# DS627-1_1-A.net
KiCad netlist of a schematic drawn in Altium Designer
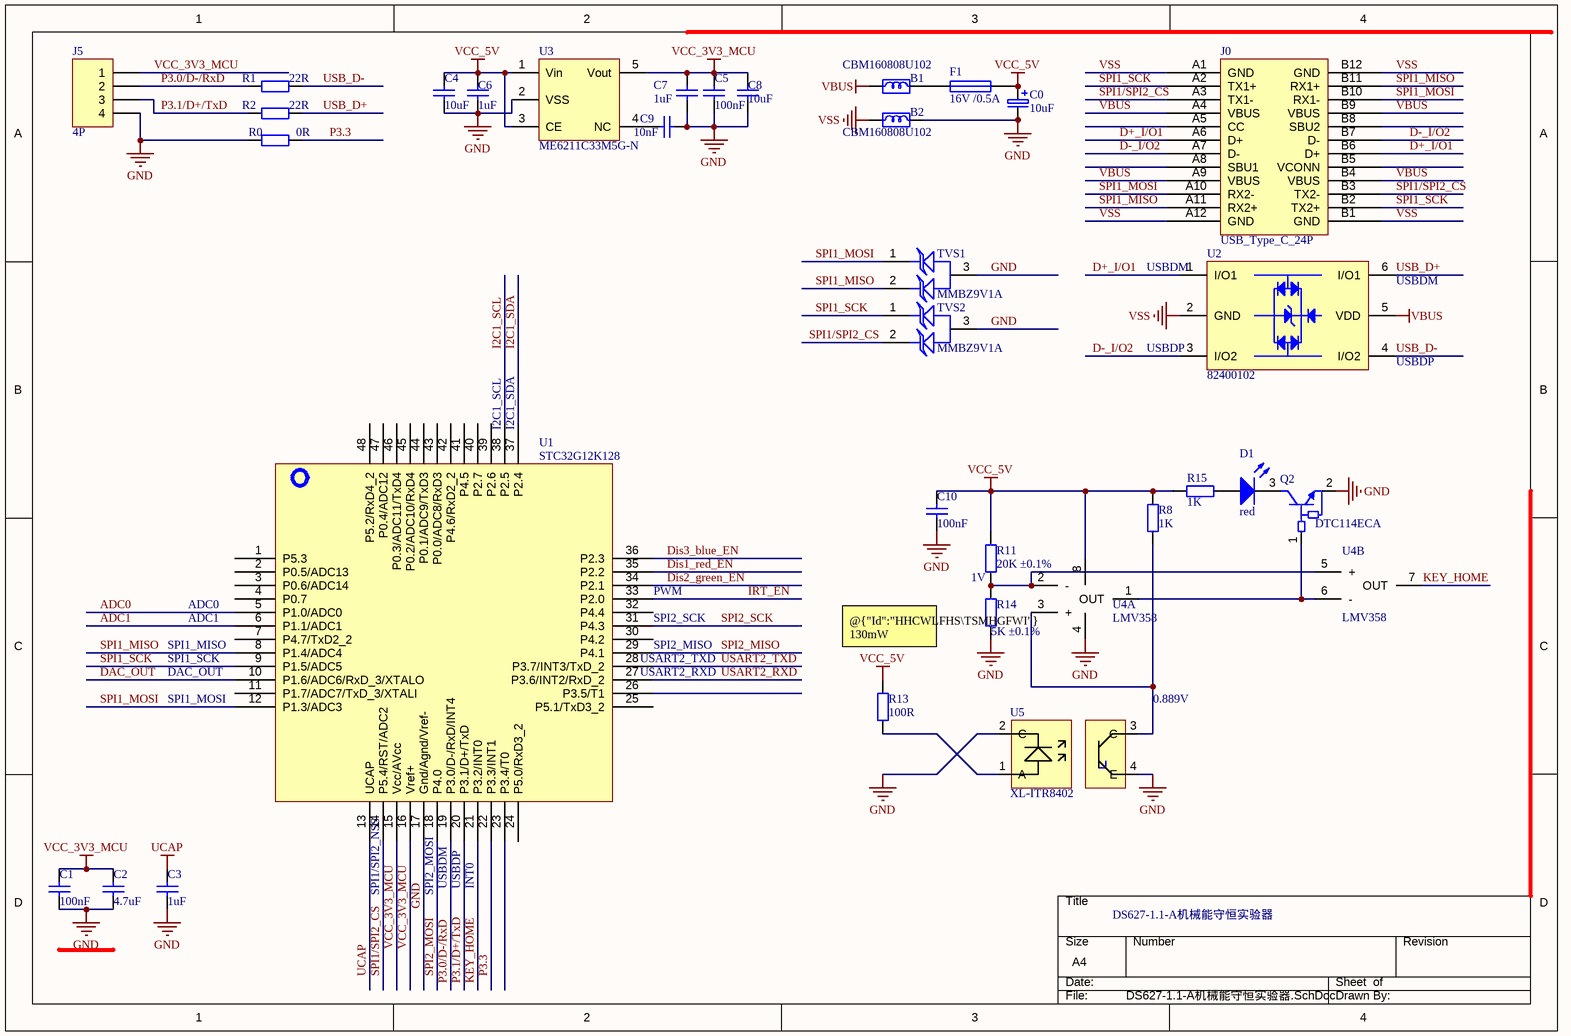
[diagram p0: DS627-1.1-A机械能守恒实验器.SchDoc]

(export (version "E")
  (design (tool "Eeschema 10.0.6"))
  (components
    (comp (ref "B1")
      (value "CBM160808U102")
      (footprint "0603Bead")
      (description "贴片磁珠")
      (libsource (lib "AD_SCH") (part "Chip Ferrite Bead 0606"))
    )
    (comp (ref "B2")
      (value "CBM160808U102")
      (footprint "0603Bead")
      (description "贴片磁珠")
      (libsource (lib "AD_SCH") (part "Chip Ferrite Bead 0606"))
    )
    (comp (ref "C0")
      (value "10uF")
      (footprint "AVX_3216-18(1206)_SMD")
      (description "钽电容")
      (fields (field (name "Comment") "AVX_10uF/16V ±10％(C106)"))
      (libsource (lib "AD_SCH") (part "AVX_10uF/16V ±10％(C106)"))
    )
    (comp (ref "C1")
      (value "100nF")
      (footprint "0603CAP")
      (description "贴片电容")
      (fields (field (name "Comment") "SMDCAP00013"))
      (libsource (lib "AD_SCH") (part "MLCC 100nF 50V ±10％ 0603"))
    )
    (comp (ref "C2")
      (value "4.7uF")
      (footprint "0603CAP")
      (description "贴片电容")
      (fields (field (name "Comment") "SMDCAP00012"))
      (libsource (lib "AD_SCH") (part "MLCC 4.7uF 50V ±10％ 0603"))
    )
    (comp (ref "C3")
      (value "1uF")
      (footprint "0603CAP")
      (description "贴片电容")
      (fields (field (name "Comment") "SMDCAP00015"))
      (libsource (lib "AD_SCH") (part "MLCC 1uF 50V ±10％ 0603"))
    )
    (comp (ref "C4")
      (value "10uF")
      (footprint "1206CAP")
      (description "贴片电容")
      (fields (field (name "Comment") "MLCC 10uF 50V ±20％ 1206"))
      (libsource (lib "AD_SCH") (part "MLCC 10uF 50V ±20％ 1206"))
    )
    (comp (ref "C5")
      (value "100nF")
      (footprint "0603CAP")
      (description "贴片电容")
      (fields (field (name "Comment") "SMDCAP00013"))
      (libsource (lib "AD_SCH") (part "MLCC 100nF 50V ±10％ 0603"))
    )
    (comp (ref "C6")
      (value "1uF")
      (footprint "0603CAP")
      (description "贴片电容")
      (fields (field (name "Comment") "SMDCAP00015"))
      (libsource (lib "AD_SCH") (part "MLCC 1uF 50V ±10％ 0603"))
    )
    (comp (ref "C7")
      (value "1uF")
      (footprint "0603CAP")
      (description "贴片电容")
      (fields (field (name "Comment") "SMDCAP00015"))
      (libsource (lib "AD_SCH") (part "MLCC 1uF 50V ±10％ 0603"))
    )
    (comp (ref "C8")
      (value "10uF")
      (footprint "1206CAP")
      (description "贴片电容")
      (fields (field (name "Comment") "MLCC 10uF 50V ±20％ 1206"))
      (libsource (lib "AD_SCH") (part "MLCC 10uF 50V ±20％ 1206"))
    )
    (comp (ref "C9")
      (value "10nF")
      (footprint "0603CAP")
      (description "贴片电容")
      (fields (field (name "Comment") "SMDCAP00010"))
      (libsource (lib "AD_SCH") (part "MLCC 10nF 50V ±10％ 0603"))
    )
    (comp (ref "C10")
      (value "100nF")
      (footprint "0603CAP")
      (description "贴片电容")
      (fields (field (name "Comment") "SMDCAP00013"))
      (libsource (lib "AD_SCH") (part "MLCC 100nF 50V ±10％ 0603"))
    )
    (comp (ref "D1")
      (value "red")
      (footprint "LED_3mm_red")
      (description "插件LED")
      (fields (field (name "Comment") "Φ3 透明发红 DIP2"))
      (libsource (lib "AD_SCH") (part "Φ3 透明发红 DIP2"))
    )
    (comp (ref "F1")
      (value "16V /0.5A")
      (footprint "1206FUSE")
      (description "贴片自恢复保险丝 16V /0.5A")
      (fields (field (name "Comment") "SMD1206-050C-16V"))
      (libsource (lib "AD_SCH") (part "SMD1206-050C-16V"))
    )
    (comp (ref "J0")
      (value "USB_Type_C_24P")
      (footprint "USB_TYPE_C_24P_Receptacle")
      (libsource (lib "AD_SCH") (part "USB_Type_C_24P"))
    )
    (comp (ref "J5")
      (value "4P")
      (footprint "H4")
      (description "单排直针")
      (fields (field (name "Comment") "DIP4单排直针  间距2mm 针长11mm 铜"))
      (libsource (lib "AD_SCH") (part "DIP4单排直针  间距2mm 针长11mm 铜"))
    )
    (comp (ref "Q2")
      (value "DTC114ECA")
      (footprint "SOT23")
      (description "数字晶体管")
      (fields (field (name "Comment") "SMDIC000037"))
      (libsource (lib "AD_SCH") (part "DTC114ECA SOT-23 长电"))
    )
    (comp (ref "R0")
      (value "0R")
      (footprint "0603RES")
      (description "贴片电阻")
      (fields (field (name "Comment") "Chip 0R 1/16W ±1％ 0603"))
      (libsource (lib "AD_SCH") (part "Chip 0R 1/16W ±1％ 0603"))
    )
    (comp (ref "R1")
      (value "22R")
      (footprint "0603RES")
      (description "贴片电阻")
      (fields (field (name "Comment") "Chip 22R 1/16W ±1％ 0603"))
      (libsource (lib "AD_SCH") (part "Chip 22R 1/16W ±1％ 0603"))
    )
    (comp (ref "R2")
      (value "22R")
      (footprint "0603RES")
      (description "贴片电阻")
      (fields (field (name "Comment") "Chip 22R 1/16W ±1％ 0603"))
      (libsource (lib "AD_SCH") (part "Chip 22R 1/16W ±1％ 0603"))
    )
    (comp (ref "R8")
      (value "1K")
      (footprint "0603RES")
      (description "贴片电阻")
      (fields (field (name "Comment") "Chip 1K 1/16W ±1％ 0603"))
      (libsource (lib "") (part "Chip 1K 1/16W ±1％ 0603_1"))
    )
    (comp (ref "R11")
      (value "20K ±0.1%")
      (footprint "0603RES")
      (fields (field (name "Comment") "SMDRES00090"))
      (libsource (lib "AD_SCH") (part "Chip 20K 1/10W ±0.1％ 0603"))
    )
    (comp (ref "R13")
      (value "100R")
      (footprint "0805RES")
      (description "贴片电阻")
      (fields (field (name "Comment") "SMDRES00016"))
      (libsource (lib "AD_SCH") (part "Chip 100R 1/10W ±1％ 0805"))
    )
    (comp (ref "R14")
      (value "5K ±0.1%")
      (footprint "0603RES")
      (fields (field (name "Comment") "SMDRES00034"))
      (libsource (lib "AD_SCH") (part "Chip 5K 1/10W ±0.1％ 0603"))
    )
    (comp (ref "R15")
      (value "1K")
      (footprint "0603RES")
      (description "贴片电阻")
      (fields (field (name "Comment") "SMDRES00034"))
      (libsource (lib "AD_SCH") (part "Chip 1K 1/16W ±1％ 0603"))
    )
    (comp (ref "TVS1")
      (value "MMBZ9V1A")
      (footprint "SOT23")
      (description "瞬态抑制二极管")
      (libsource (lib "AD_SCH") (part "TVS"))
    )
    (comp (ref "TVS2")
      (value "MMBZ9V1A")
      (footprint "SOT23")
      (description "瞬态抑制二极管")
      (libsource (lib "AD_SCH") (part "TVS"))
    )
    (comp (ref "U1")
      (value "STC32G12K128")
      (footprint "LQFP-48")
      (description "单片机芯片")
      (fields (field (name "Comment") "STC32G12K128_35I LQFP48"))
      (libsource (lib "AD_SCH") (part "STC32G12K128_35I LQFP48"))
    )
    (comp (ref "U2")
      (value "82400102")
      (footprint "SOT23-6")
      (description "瞬态抑制二极管(TVS)")
      (libsource (lib "AD_SCH") (part "82400102"))
    )
    (comp (ref "U3")
      (value "ME6211C33M5G-N")
      (footprint "SOT23-5")
      (description "稳压芯片")
      (libsource (lib "AD_SCH") (part "ME6211C33M5G-N"))
    )
    (comp (ref "U4")
      (value "LMV358")
      (footprint "SO-8")
      (description "双路、5.5V、1MHz、4mV 失调电压、RRO 运算放大器")
      (fields (field (name "Comment") "LMV358IDGKR  VSSOP-8"))
      (libsource (lib "AD_SCH") (part "LMV358IDGKR  VSSOP-8"))
    )
    (comp (ref "U5")
      (value "XL-ITR8402")
      (footprint "XL-ITR8402_L14.0-W6.0")
      (description "光电开关")
      (libsource (lib "AD_SCH") (part "XL-ITR8402"))
    )
  )
  (nets
    (net (code "1") (name "/ADC0") (class "Default")
      (node (ref "U1") (pin "5") (pinfunction "P1.0/ADC0_5") (pintype "passive"))
    )
    (net (code "2") (name "/ADC1") (class "Default")
      (node (ref "U1") (pin "6") (pinfunction "P1.1/ADC1_6") (pintype "passive"))
    )
    (net (code "3") (name "/D+_I{slash}O1") (class "Default")
      (node (ref "J0") (pin "A6") (pinfunction "D+_A6") (pintype "passive"))
      (node (ref "J0") (pin "B6") (pinfunction "D+_B6") (pintype "passive"))
      (node (ref "U2") (pin "1") (pinfunction "I/O1_1") (pintype "passive"))
    )
    (net (code "4") (name "/D-_I{slash}O2") (class "Default")
      (node (ref "J0") (pin "A7") (pinfunction "D-_A7") (pintype "passive"))
      (node (ref "J0") (pin "B7") (pinfunction "D-_B7") (pintype "passive"))
      (node (ref "U2") (pin "3") (pinfunction "I/O2_3") (pintype "passive"))
    )
    (net (code "5") (name "/DAC_OUT") (class "Default")
      (node (ref "U1") (pin "10") (pinfunction "P1.6/ADC6/RxD_3/XTALO_10") (pintype "passive"))
    )
    (net (code "6") (name "/Dis1_red_EN") (class "Default")
      (node (ref "U1") (pin "35") (pinfunction "P2.2_35") (pintype "passive"))
    )
    (net (code "7") (name "/Dis2_green_EN") (class "Default")
      (node (ref "U1") (pin "34") (pinfunction "P2.1_34") (pintype "passive"))
    )
    (net (code "8") (name "/Dis3_blue_EN") (class "Default")
      (node (ref "U1") (pin "36") (pinfunction "P2.3_36") (pintype "passive"))
    )
    (net (code "9") (name "/I2C1_SCL") (class "Default")
      (node (ref "U1") (pin "38") (pinfunction "P2.5_38") (pintype "passive"))
    )
    (net (code "10") (name "/I2C1_SDA") (class "Default")
      (node (ref "U1") (pin "37") (pinfunction "P2.4_37") (pintype "passive"))
    )
    (net (code "11") (name "/IRT_EN") (class "Default")
      (node (ref "U1") (pin "33") (pinfunction "P2.0_33") (pintype "passive"))
    )
    (net (code "12") (name "/KEY_HOME") (class "Default")
      (node (ref "U1") (pin "21") (pinfunction "P3.2/INT0_21") (pintype "passive"))
      (node (ref "U4") (pin "7") (pinfunction "OUT_7") (pintype "passive"))
    )
    (net (code "13") (name "/P3.0{slash}D-{slash}RxD") (class "Default")
      (node (ref "J5") (pin "2") (pinfunction "2_2") (pintype "passive"))
      (node (ref "R1") (pin "1") (pinfunction "1_1") (pintype "passive"))
      (node (ref "U1") (pin "19") (pinfunction "P3.0/D-/RxD/INT4_19") (pintype "passive"))
    )
    (net (code "14") (name "/P3.1{slash}D+{slash}TxD") (class "Default")
      (node (ref "J5") (pin "3") (pinfunction "3_3") (pintype "passive"))
      (node (ref "R2") (pin "1") (pinfunction "1_1") (pintype "passive"))
      (node (ref "U1") (pin "20") (pinfunction "P3.1/D+/TxD_20") (pintype "passive"))
    )
    (net (code "15") (name "/P3.3") (class "Default")
      (node (ref "R0") (pin "2") (pinfunction "2_2") (pintype "passive"))
      (node (ref "U1") (pin "22") (pinfunction "P3.3/INT1_22") (pintype "passive"))
    )
    (net (code "16") (name "/SPI1_MISO") (class "Default")
      (node (ref "J0") (pin "A11") (pinfunction "RX2+_A11") (pintype "passive"))
      (node (ref "J0") (pin "B11") (pinfunction "RX1+_B11") (pintype "passive"))
      (node (ref "TVS1") (pin "2") (pinfunction "2_2") (pintype "passive"))
      (node (ref "U1") (pin "8") (pinfunction "P1.4/ADC4_8") (pintype "passive"))
    )
    (net (code "17") (name "/SPI1_MOSI") (class "Default")
      (node (ref "J0") (pin "A10") (pinfunction "RX2-_A10") (pintype "passive"))
      (node (ref "J0") (pin "B10") (pinfunction "RX1-_B10") (pintype "passive"))
      (node (ref "TVS1") (pin "1") (pinfunction "1_1") (pintype "passive"))
      (node (ref "U1") (pin "12") (pinfunction "P1.3/ADC3_12") (pintype "passive"))
    )
    (net (code "18") (name "/SPI1_SCK") (class "Default")
      (node (ref "J0") (pin "A2") (pinfunction "TX1+_A2") (pintype "passive"))
      (node (ref "J0") (pin "B2") (pinfunction "TX2+_B2") (pintype "passive"))
      (node (ref "TVS2") (pin "1") (pinfunction "1_1") (pintype "passive"))
      (node (ref "U1") (pin "9") (pinfunction "P1.5/ADC5_9") (pintype "passive"))
    )
    (net (code "19") (name "/SPI1{slash}SPI2_CS") (class "Default")
      (node (ref "J0") (pin "A3") (pinfunction "TX1-_A3") (pintype "passive"))
      (node (ref "J0") (pin "B3") (pinfunction "TX2-_B3") (pintype "passive"))
      (node (ref "TVS2") (pin "2") (pinfunction "2_2") (pintype "passive"))
      (node (ref "U1") (pin "14") (pinfunction "P5.4/RST/ADC2_14") (pintype "passive"))
    )
    (net (code "20") (name "/SPI2_MISO") (class "Default")
      (node (ref "U1") (pin "29") (pinfunction "P4.1_29") (pintype "passive"))
    )
    (net (code "21") (name "/SPI2_MOSI") (class "Default")
      (node (ref "U1") (pin "18") (pinfunction "P4.0_18") (pintype "passive"))
    )
    (net (code "22") (name "/SPI2_SCK") (class "Default")
      (node (ref "U1") (pin "31") (pinfunction "P4.3_31") (pintype "passive"))
    )
    (net (code "23") (name "/USART2_RXD") (class "Default")
      (node (ref "U1") (pin "27") (pinfunction "P3.6/INT2/RxD_2_27") (pintype "passive"))
    )
    (net (code "24") (name "/USART2_TXD") (class "Default")
      (node (ref "U1") (pin "28") (pinfunction "P3.7/INT3/TxD_2_28") (pintype "passive"))
    )
    (net (code "25") (name "/USB_D+") (class "Default")
      (node (ref "R2") (pin "2") (pinfunction "2_2") (pintype "passive"))
      (node (ref "U2") (pin "6") (pinfunction "I/O1_6") (pintype "passive"))
    )
    (net (code "26") (name "/USB_D-") (class "Default")
      (node (ref "R1") (pin "2") (pinfunction "2_2") (pintype "passive"))
      (node (ref "U2") (pin "4") (pinfunction "I/O2_4") (pintype "passive"))
    )
    (net (code "27") (name "GND") (class "Default")
      (node (ref "B2") (pin "2") (pinfunction "2_2") (pintype "passive"))
      (node (ref "C0") (pin "2") (pinfunction "2_2") (pintype "passive"))
      (node (ref "C1") (pin "1") (pinfunction "1_1") (pintype "passive"))
      (node (ref "C10") (pin "1") (pinfunction "1_1") (pintype "passive"))
      (node (ref "C2") (pin "1") (pinfunction "1_1") (pintype "passive"))
      (node (ref "C3") (pin "1") (pinfunction "1_1") (pintype "passive"))
      (node (ref "C4") (pin "1") (pinfunction "1_1") (pintype "passive"))
      (node (ref "C5") (pin "1") (pinfunction "1_1") (pintype "passive"))
      (node (ref "C6") (pin "1") (pinfunction "1_1") (pintype "passive"))
      (node (ref "C7") (pin "1") (pinfunction "1_1") (pintype "passive"))
      (node (ref "C8") (pin "1") (pinfunction "1_1") (pintype "passive"))
      (node (ref "C9") (pin "2") (pinfunction "2_2") (pintype "passive"))
      (node (ref "J5") (pin "4") (pinfunction "4_4") (pintype "passive"))
      (node (ref "Q2") (pin "2") (pinfunction "GND_2") (pintype "passive"))
      (node (ref "R0") (pin "1") (pinfunction "1_1") (pintype "passive"))
      (node (ref "R14") (pin "1") (pinfunction "1_1") (pintype "passive"))
      (node (ref "TVS1") (pin "3") (pinfunction "3_3") (pintype "passive"))
      (node (ref "TVS2") (pin "3") (pinfunction "3_3") (pintype "passive"))
      (node (ref "U1") (pin "17") (pinfunction "Gnd/Agnd/Vref-_17") (pintype "passive"))
      (node (ref "U3") (pin "2") (pinfunction "VSS_2") (pintype "passive"))
      (node (ref "U4") (pin "4") (pinfunction "GND_4") (pintype "passive"))
      (node (ref "U5") (pin "2") (pinfunction "C_2") (pintype "passive"))
      (node (ref "U5") (pin "4") (pinfunction "E_4") (pintype "passive"))
    )
    (net (code "28") (name "Net-(B1-Pad2)") (class "Default")
      (node (ref "B1") (pin "2") (pinfunction "2_2") (pintype "passive"))
      (node (ref "F1") (pin "1") (pinfunction "1_1") (pintype "passive"))
    )
    (net (code "29") (name "Net-(D1-A)") (class "Default")
      (node (ref "D1") (pin "1") (pinfunction "A_1") (pintype "passive"))
      (node (ref "R15") (pin "1") (pinfunction "1_1") (pintype "passive"))
    )
    (net (code "30") (name "Net-(D1-K)") (class "Default")
      (node (ref "D1") (pin "2") (pinfunction "K_2") (pintype "passive"))
      (node (ref "Q2") (pin "3") (pinfunction "OUT_3") (pintype "passive"))
    )
    (net (code "31") (name "Net-(Q2-IN)") (class "Default")
      (node (ref "Q2") (pin "1") (pinfunction "IN_1") (pintype "passive"))
      (node (ref "U4") (pin "1") (pinfunction "OUT_1") (pintype "passive"))
      (node (ref "U4") (pin "6") (pinfunction "-_6") (pintype "passive"))
    )
    (net (code "32") (name "Net-(U3-NC)") (class "Default")
      (node (ref "C9") (pin "1") (pinfunction "1_1") (pintype "passive"))
      (node (ref "U3") (pin "4") (pinfunction "NC_4") (pintype "passive"))
    )
    (net (code "33") (name "Net-(U4A-+)") (class "Default")
      (node (ref "R8") (pin "1") (pinfunction "1_1") (pintype "passive"))
      (node (ref "U4") (pin "3") (pinfunction "+_3") (pintype "passive"))
      (node (ref "U5") (pin "3") (pinfunction "C_3") (pintype "passive"))
    )
    (net (code "34") (name "Net-(U4A--)") (class "Default")
      (node (ref "R11") (pin "1") (pinfunction "1_1") (pintype "passive"))
      (node (ref "R14") (pin "2") (pinfunction "2_2") (pintype "passive"))
      (node (ref "U4") (pin "2") (pinfunction "-_2") (pintype "passive"))
      (node (ref "U4") (pin "5") (pinfunction "+_5") (pintype "passive"))
    )
    (net (code "35") (name "Net-(U5-A)") (class "Default")
      (node (ref "R13") (pin "1") (pinfunction "1_1") (pintype "passive"))
      (node (ref "U5") (pin "1") (pinfunction "A_1") (pintype "passive"))
    )
    (net (code "36") (name "UCAP") (class "Default")
      (node (ref "C3") (pin "2") (pinfunction "2_2") (pintype "passive"))
      (node (ref "U1") (pin "13") (pinfunction "UCAP_13") (pintype "passive"))
    )
    (net (code "37") (name "VBUS") (class "Default")
      (node (ref "B1") (pin "1") (pinfunction "1_1") (pintype "passive"))
      (node (ref "J0") (pin "A4") (pinfunction "VBUS_A4") (pintype "passive"))
      (node (ref "J0") (pin "A9") (pinfunction "VBUS_A9") (pintype "passive"))
      (node (ref "J0") (pin "B4") (pinfunction "VBUS_B4") (pintype "passive"))
      (node (ref "J0") (pin "B9") (pinfunction "VBUS_B9") (pintype "passive"))
      (node (ref "U2") (pin "5") (pinfunction "VDD_5") (pintype "passive"))
    )
    (net (code "38") (name "VCC_3V3_MCU") (class "Default")
      (node (ref "C1") (pin "2") (pinfunction "2_2") (pintype "passive"))
      (node (ref "C2") (pin "2") (pinfunction "2_2") (pintype "passive"))
      (node (ref "C5") (pin "2") (pinfunction "2_2") (pintype "passive"))
      (node (ref "C7") (pin "2") (pinfunction "2_2") (pintype "passive"))
      (node (ref "C8") (pin "2") (pinfunction "2_2") (pintype "passive"))
      (node (ref "J5") (pin "1") (pinfunction "1_1") (pintype "passive"))
      (node (ref "U1") (pin "15") (pinfunction "Vcc/AVcc_15") (pintype "passive"))
      (node (ref "U1") (pin "16") (pinfunction "Vref+_16") (pintype "passive"))
      (node (ref "U3") (pin "5") (pinfunction "Vout_5") (pintype "passive"))
    )
    (net (code "39") (name "VCC_5V") (class "Default")
      (node (ref "C0") (pin "1") (pinfunction "1_1") (pintype "passive"))
      (node (ref "C10") (pin "2") (pinfunction "2_2") (pintype "passive"))
      (node (ref "C4") (pin "2") (pinfunction "2_2") (pintype "passive"))
      (node (ref "C6") (pin "2") (pinfunction "2_2") (pintype "passive"))
      (node (ref "F1") (pin "2") (pinfunction "2_2") (pintype "passive"))
      (node (ref "R11") (pin "2") (pinfunction "2_2") (pintype "passive"))
      (node (ref "R13") (pin "2") (pinfunction "2_2") (pintype "passive"))
      (node (ref "R15") (pin "2") (pinfunction "2_2") (pintype "passive"))
      (node (ref "R8") (pin "2") (pinfunction "2_2") (pintype "passive"))
      (node (ref "U3") (pin "1") (pinfunction "Vin_1") (pintype "passive"))
      (node (ref "U3") (pin "3") (pinfunction "CE_3") (pintype "passive"))
      (node (ref "U4") (pin "8") (pinfunction "VCC_8") (pintype "passive"))
    )
    (net (code "40") (name "VSS") (class "Default")
      (node (ref "B2") (pin "1") (pinfunction "1_1") (pintype "passive"))
      (node (ref "J0") (pin "A1") (pinfunction "GND_A1") (pintype "passive"))
      (node (ref "J0") (pin "A12") (pinfunction "GND_A12") (pintype "passive"))
      (node (ref "J0") (pin "B1") (pinfunction "GND_B1") (pintype "passive"))
      (node (ref "J0") (pin "B12") (pinfunction "GND_B12") (pintype "passive"))
      (node (ref "U2") (pin "2") (pinfunction "GND_2") (pintype "passive"))
    )
    (net (code "41") (name "unconnected-(J0-CC-PadA5)") (class "Default")
      (node (ref "J0") (pin "A5") (pinfunction "CC_A5") (pintype "passive"))
    )
    (net (code "42") (name "unconnected-(J0-SBU1-PadA8)") (class "Default")
      (node (ref "J0") (pin "A8") (pinfunction "SBU1_A8") (pintype "passive"))
    )
    (net (code "43") (name "unconnected-(J0-SBU2-PadB8)") (class "Default")
      (node (ref "J0") (pin "B8") (pinfunction "SBU2_B8") (pintype "passive"))
    )
    (net (code "44") (name "unconnected-(J0-VCONN-PadB5)") (class "Default")
      (node (ref "J0") (pin "B5") (pinfunction "VCONN_B5") (pintype "passive"))
    )
    (net (code "45") (name "unconnected-(U1-P0.0{slash}ADC8{slash}RxD3-Pad43)") (class "Default")
      (node (ref "U1") (pin "43") (pinfunction "P0.0/ADC8/RxD3_43") (pintype "passive"))
    )
    (net (code "46") (name "unconnected-(U1-P0.1{slash}ADC9{slash}TxD3-Pad44)") (class "Default")
      (node (ref "U1") (pin "44") (pinfunction "P0.1/ADC9/TxD3_44") (pintype "passive"))
    )
    (net (code "47") (name "unconnected-(U1-P0.2{slash}ADC10{slash}RxD4-Pad45)") (class "Default")
      (node (ref "U1") (pin "45") (pinfunction "P0.2/ADC10/RxD4_45") (pintype "passive"))
    )
    (net (code "48") (name "unconnected-(U1-P0.3{slash}ADC11{slash}TxD4-Pad46)") (class "Default")
      (node (ref "U1") (pin "46") (pinfunction "P0.3/ADC11/TxD4_46") (pintype "passive"))
    )
    (net (code "49") (name "unconnected-(U1-P0.4{slash}ADC12-Pad47)") (class "Default")
      (node (ref "U1") (pin "47") (pinfunction "P0.4/ADC12_47") (pintype "passive"))
    )
    (net (code "50") (name "unconnected-(U1-P0.5{slash}ADC13-Pad2)") (class "Default")
      (node (ref "U1") (pin "2") (pinfunction "P0.5/ADC13_2") (pintype "passive"))
    )
    (net (code "51") (name "unconnected-(U1-P0.6{slash}ADC14-Pad3)") (class "Default")
      (node (ref "U1") (pin "3") (pinfunction "P0.6/ADC14_3") (pintype "passive"))
    )
    (net (code "52") (name "unconnected-(U1-P0.7-Pad4)") (class "Default")
      (node (ref "U1") (pin "4") (pinfunction "P0.7_4") (pintype "passive"))
    )
    (net (code "53") (name "unconnected-(U1-P1.7{slash}ADC7{slash}TxD_3{slash}XTALI-Pad11)") (class "Default")
      (node (ref "U1") (pin "11") (pinfunction "P1.7/ADC7/TxD_3/XTALI_11") (pintype "passive"))
    )
    (net (code "54") (name "unconnected-(U1-P2.6-Pad39)") (class "Default")
      (node (ref "U1") (pin "39") (pinfunction "P2.6_39") (pintype "passive"))
    )
    (net (code "55") (name "unconnected-(U1-P2.7-Pad40)") (class "Default")
      (node (ref "U1") (pin "40") (pinfunction "P2.7_40") (pintype "passive"))
    )
    (net (code "56") (name "unconnected-(U1-P3.4{slash}T0-Pad23)") (class "Default")
      (node (ref "U1") (pin "23") (pinfunction "P3.4/T0_23") (pintype "passive"))
    )
    (net (code "57") (name "unconnected-(U1-P3.5{slash}T1-Pad26)") (class "Default")
      (node (ref "U1") (pin "26") (pinfunction "P3.5/T1_26") (pintype "passive"))
    )
    (net (code "58") (name "unconnected-(U1-P4.2-Pad30)") (class "Default")
      (node (ref "U1") (pin "30") (pinfunction "P4.2_30") (pintype "passive"))
    )
    (net (code "59") (name "unconnected-(U1-P4.4-Pad32)") (class "Default")
      (node (ref "U1") (pin "32") (pinfunction "P4.4_32") (pintype "passive"))
    )
    (net (code "60") (name "unconnected-(U1-P4.5-Pad41)") (class "Default")
      (node (ref "U1") (pin "41") (pinfunction "P4.5_41") (pintype "passive"))
    )
    (net (code "61") (name "unconnected-(U1-P4.6{slash}RxD2_2-Pad42)") (class "Default")
      (node (ref "U1") (pin "42") (pinfunction "P4.6/RxD2_2_42") (pintype "passive"))
    )
    (net (code "62") (name "unconnected-(U1-P4.7{slash}TxD2_2-Pad7)") (class "Default")
      (node (ref "U1") (pin "7") (pinfunction "P4.7/TxD2_2_7") (pintype "passive"))
    )
    (net (code "63") (name "unconnected-(U1-P5.0{slash}RxD3_2-Pad24)") (class "Default")
      (node (ref "U1") (pin "24") (pinfunction "P5.0/RxD3_2_24") (pintype "passive"))
    )
    (net (code "64") (name "unconnected-(U1-P5.1{slash}TxD3_2-Pad25)") (class "Default")
      (node (ref "U1") (pin "25") (pinfunction "P5.1/TxD3_2_25") (pintype "passive"))
    )
    (net (code "65") (name "unconnected-(U1-P5.2{slash}RxD4_2-Pad48)") (class "Default")
      (node (ref "U1") (pin "48") (pinfunction "P5.2/RxD4_2_48") (pintype "passive"))
    )
    (net (code "66") (name "unconnected-(U1-P5.3-Pad1)") (class "Default")
      (node (ref "U1") (pin "1") (pinfunction "P5.3_1") (pintype "passive"))
    )
  )
)
